# CapBank_Introspection.net
KiCad netlist of a schematic drawn in Altium Designer
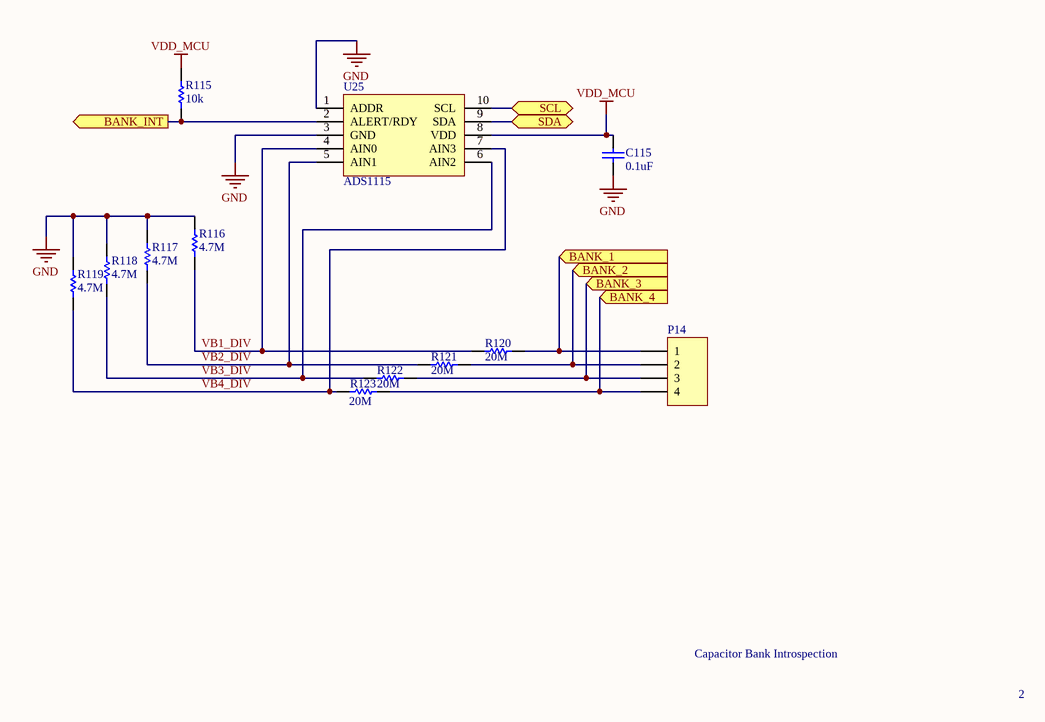
[diagram p0: CapBank_Introspection.SchDoc]

(export (version "E")
  (design (tool "Eeschema 10.0.6"))
  (components
    (comp (ref "C115")
      (value "0.1uF")
      (footprint "0603")
      (description "Ceramic Capacitor (Surface Mount)")
      (fields
        (field (name "MANUFACTURER") "Murata Electronics North America")
        (field (name "MANUFACTURER PART NUMBER") "GRM188R71C104KA01D")
      )
      (libsource (lib "DRP_Basic_2014") (part "Cap"))
    )
    (comp (ref "P14")
      (value "~")
      (footprint "MHDR1X4")
      (description "Header, 4-Pin")
      (fields
        (field (name "DIGI-KEY PART NUMBER") "952-3358-ND")
        (field (name "DISTRIBUTOR PART NUMBER") "855-M52-5000445")
        (field (name "PUBLISHER") "Altium Limited")
      )
      (libsource (lib "Miscellaneous Connectors") (part "MHDR1X4"))
    )
    (comp (ref "R115")
      (value "10k")
      (footprint "0603")
      (description "Chip Resistor (Surface Mount)")
      (fields
        (field (name "MANUFACTURER") "Yageo")
        (field (name "MANUFACTURER PART NUMBER") "RC0603FR-0710KL")
      )
      (libsource (lib "DRP_Basic_2014") (part "Res"))
    )
    (comp (ref "R116")
      (value "4.7M")
      (footprint "0603")
      (description "Chip Resistor (Surface Mount)")
      (fields
        (field (name "MANUFACTURER") "Generic Chip Res (TBD)")
        (field (name "MANUFACTURER PART NUMBER") "RC0603FR-074M7L")
      )
      (libsource (lib "DRP_Basic_2014") (part "Res"))
    )
    (comp (ref "R117")
      (value "4.7M")
      (footprint "0603")
      (description "Chip Resistor (Surface Mount)")
      (fields
        (field (name "MANUFACTURER") "Generic Chip Res (TBD)")
        (field (name "MANUFACTURER PART NUMBER") "RC0603FR-074M7L")
      )
      (libsource (lib "DRP_Basic_2014") (part "Res"))
    )
    (comp (ref "R118")
      (value "4.7M")
      (footprint "0603")
      (description "Chip Resistor (Surface Mount)")
      (fields
        (field (name "MANUFACTURER") "Generic Chip Res (TBD)")
        (field (name "MANUFACTURER PART NUMBER") "RC0603FR-074M7L")
      )
      (libsource (lib "DRP_Basic_2014") (part "Res"))
    )
    (comp (ref "R119")
      (value "4.7M")
      (footprint "0603")
      (description "Chip Resistor (Surface Mount)")
      (fields
        (field (name "MANUFACTURER") "Generic Chip Res (TBD)")
        (field (name "MANUFACTURER PART NUMBER") "RC0603FR-074M7L")
      )
      (libsource (lib "DRP_Basic_2014") (part "Res"))
    )
    (comp (ref "R120")
      (value "20M")
      (footprint "0603")
      (description "Chip Resistor (Surface Mount)")
      (fields
        (field (name "MANUFACTURER") "Vishay Dale")
        (field (name "MANUFACTURER PART NUMBER") "CRCW060320M0JPEAHR")
      )
      (libsource (lib "DRP_Basic_2014") (part "Res"))
    )
    (comp (ref "R121")
      (value "20M")
      (footprint "0603")
      (description "Chip Resistor (Surface Mount)")
      (fields
        (field (name "MANUFACTURER") "Vishay Dale")
        (field (name "MANUFACTURER PART NUMBER") "CRCW060320M0JPEAHR")
      )
      (libsource (lib "DRP_Basic_2014") (part "Res"))
    )
    (comp (ref "R122")
      (value "20M")
      (footprint "0603")
      (description "Chip Resistor (Surface Mount)")
      (fields
        (field (name "MANUFACTURER") "Vishay Dale")
        (field (name "MANUFACTURER PART NUMBER") "CRCW060320M0JPEAHR")
      )
      (libsource (lib "DRP_Basic_2014") (part "Res"))
    )
    (comp (ref "R123")
      (value "20M")
      (footprint "0603")
      (description "Chip Resistor (Surface Mount)")
      (fields
        (field (name "MANUFACTURER") "Vishay Dale")
        (field (name "MANUFACTURER PART NUMBER") "CRCW060320M0JPEAHR")
      )
      (libsource (lib "DRP_Basic_2014") (part "Res"))
    )
    (comp (ref "U25")
      (value "ADS1115")
      (footprint "VSSOP10")
      (fields
        (field (name "DISTRIBUTOR PART NUMBER") "296-38849-1-ND")
        (field (name "MANUFACTURER") "Texas Instruments")
        (field (name "MANUFACTURER PART NUMBER") "ADS1115IDGSR")
      )
      (libsource (lib "Sprite") (part "ADS1115"))
    )
  )
  (nets
    (net (code "1") (name "/BANK_1") (class "Default")
      (node (ref "P14") (pin "1") (pinfunction "1_1") (pintype "passive"))
      (node (ref "R120") (pin "2") (pinfunction "2_2") (pintype "passive"))
    )
    (net (code "2") (name "/BANK_2") (class "Default")
      (node (ref "P14") (pin "2") (pinfunction "2_2") (pintype "passive"))
      (node (ref "R121") (pin "2") (pinfunction "2_2") (pintype "passive"))
    )
    (net (code "3") (name "/BANK_3") (class "Default")
      (node (ref "P14") (pin "3") (pinfunction "3_3") (pintype "passive"))
      (node (ref "R122") (pin "2") (pinfunction "2_2") (pintype "passive"))
    )
    (net (code "4") (name "/BANK_4") (class "Default")
      (node (ref "P14") (pin "4") (pinfunction "4_4") (pintype "passive"))
      (node (ref "R123") (pin "2") (pinfunction "2_2") (pintype "passive"))
    )
    (net (code "5") (name "/BANK_INT") (class "Default")
      (node (ref "R115") (pin "1") (pinfunction "1_1") (pintype "passive"))
      (node (ref "U25") (pin "2") (pinfunction "ALERT/RDY_2") (pintype "passive"))
    )
    (net (code "6") (name "/SCL") (class "Default")
      (node (ref "U25") (pin "10") (pinfunction "SCL_10") (pintype "open_collector"))
    )
    (net (code "7") (name "/SDA") (class "Default")
      (node (ref "U25") (pin "9") (pinfunction "SDA_9") (pintype "open_collector"))
    )
    (net (code "8") (name "/VB1_DIV") (class "Default")
      (node (ref "R116") (pin "1") (pinfunction "1_1") (pintype "passive"))
      (node (ref "R120") (pin "1") (pinfunction "1_1") (pintype "passive"))
      (node (ref "U25") (pin "4") (pinfunction "AIN0_4") (pintype "passive"))
    )
    (net (code "9") (name "/VB2_DIV") (class "Default")
      (node (ref "R117") (pin "1") (pinfunction "1_1") (pintype "passive"))
      (node (ref "R121") (pin "1") (pinfunction "1_1") (pintype "passive"))
      (node (ref "U25") (pin "5") (pinfunction "AIN1_5") (pintype "passive"))
    )
    (net (code "10") (name "/VB3_DIV") (class "Default")
      (node (ref "R118") (pin "1") (pinfunction "1_1") (pintype "passive"))
      (node (ref "R122") (pin "1") (pinfunction "1_1") (pintype "passive"))
      (node (ref "U25") (pin "6") (pinfunction "AIN2_6") (pintype "passive"))
    )
    (net (code "11") (name "/VB4_DIV") (class "Default")
      (node (ref "R119") (pin "1") (pinfunction "1_1") (pintype "passive"))
      (node (ref "R123") (pin "1") (pinfunction "1_1") (pintype "passive"))
      (node (ref "U25") (pin "7") (pinfunction "AIN3_7") (pintype "passive"))
    )
    (net (code "12") (name "GND") (class "Default")
      (node (ref "C115") (pin "1") (pinfunction "1_1") (pintype "passive"))
      (node (ref "R116") (pin "2") (pinfunction "2_2") (pintype "passive"))
      (node (ref "R117") (pin "2") (pinfunction "2_2") (pintype "passive"))
      (node (ref "R118") (pin "2") (pinfunction "2_2") (pintype "passive"))
      (node (ref "R119") (pin "2") (pinfunction "2_2") (pintype "passive"))
      (node (ref "U25") (pin "1") (pinfunction "ADDR_1") (pintype "passive"))
      (node (ref "U25") (pin "3") (pinfunction "GND_3") (pintype "passive"))
    )
    (net (code "13") (name "VDD_MCU") (class "Default")
      (node (ref "C115") (pin "2") (pinfunction "2_2") (pintype "passive"))
      (node (ref "R115") (pin "2") (pinfunction "2_2") (pintype "passive"))
      (node (ref "U25") (pin "8") (pinfunction "VDD_8") (pintype "passive"))
    )
  )
)
